# keychange.net
KiCad netlist of a schematic drawn in EAGLE
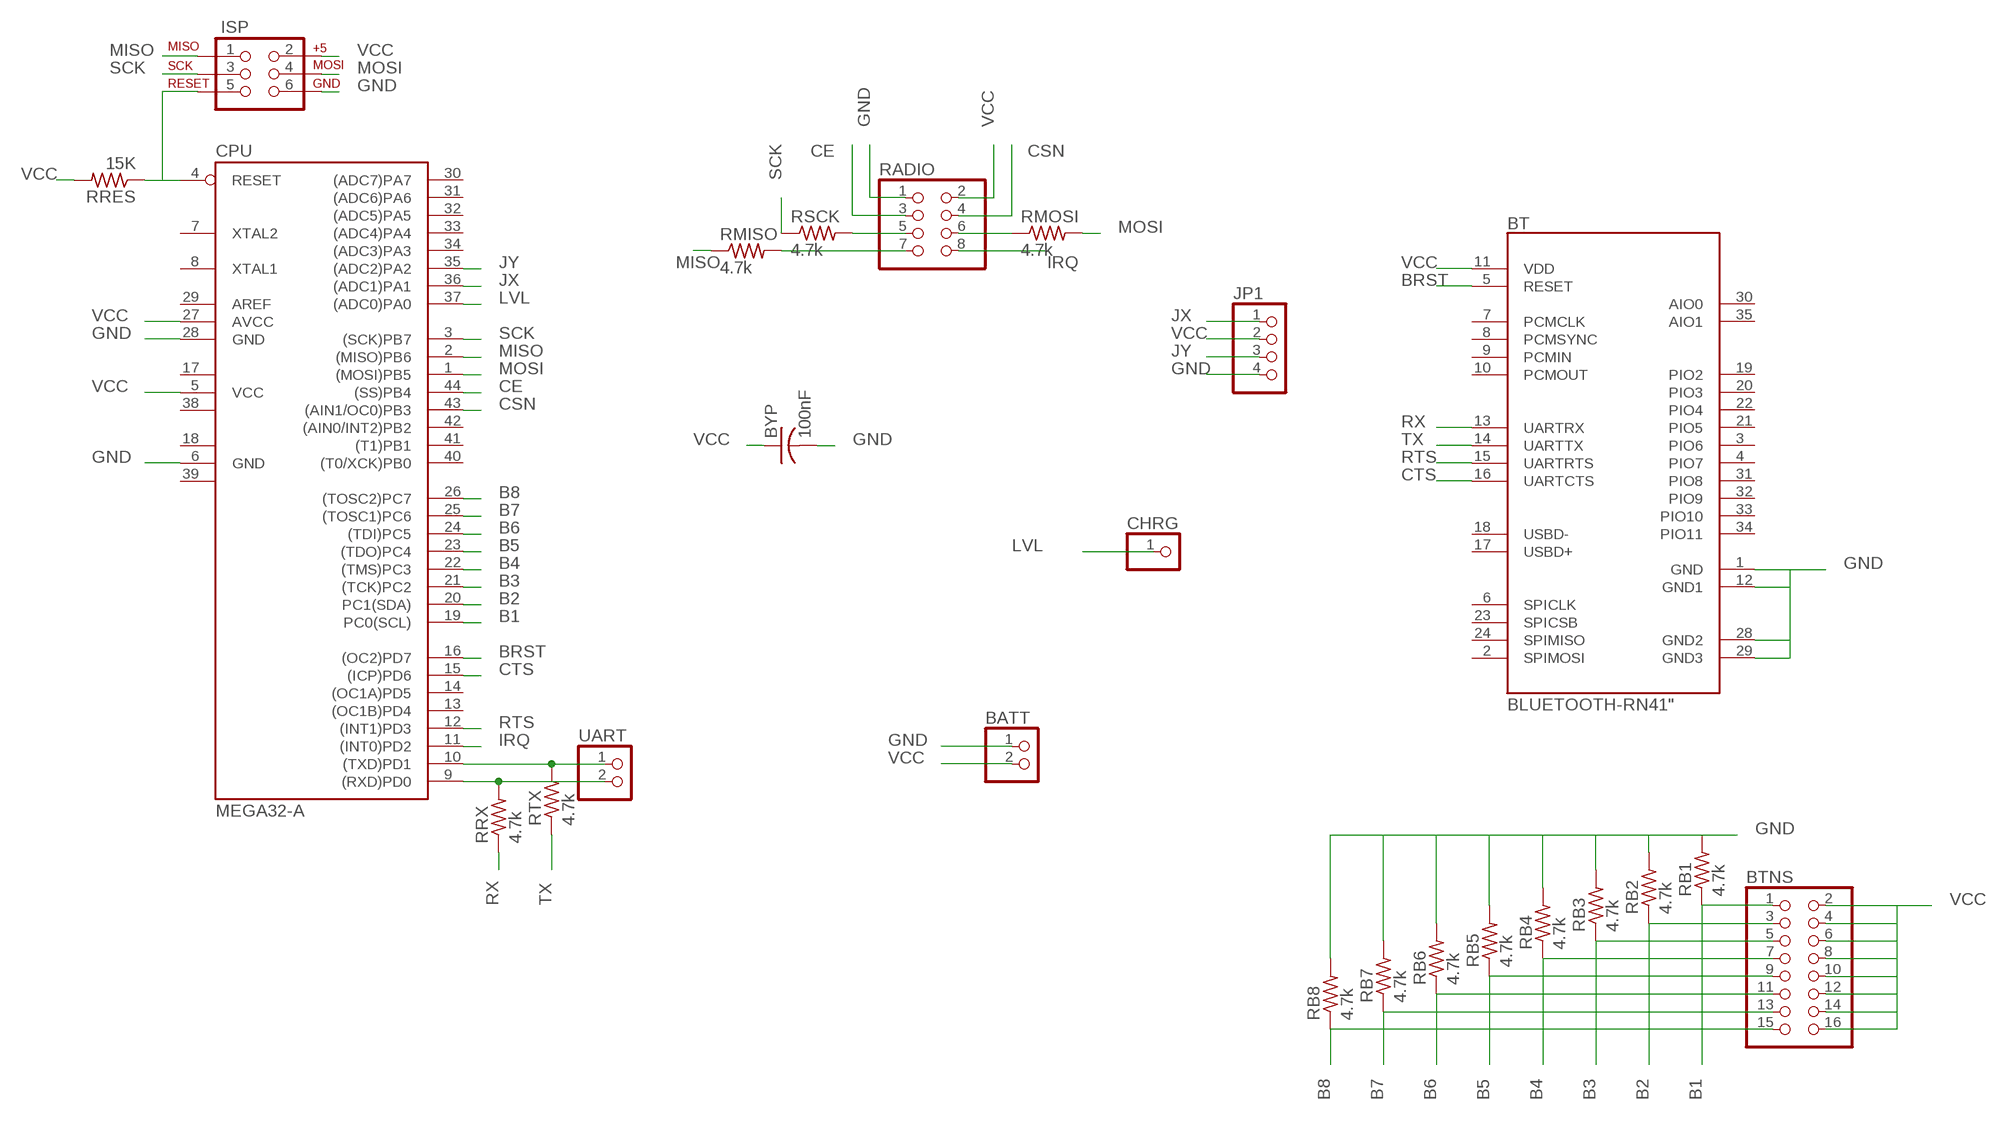
[diagram p0: schematic, sheet 1]

(export (version "E")
  (design (tool "Eeschema 10.0.6"))
  (components
    (comp (ref "BATT")
      (value "PINHD-1X2")
      (footprint "eagle-import:1X02")
      (libsource (lib "eagle-import") (part "PINHD-1X2"))
    )
    (comp (ref "BT")
      (value "BLUETOOTH-RN41\"")
      (footprint "eagle-import:RN41")
      (libsource (lib "eagle-import") (part "BLUETOOTH-RN41{dblquote}"))
    )
    (comp (ref "BTNS")
      (value "PINHD-2X8")
      (footprint "eagle-import:2X08")
      (libsource (lib "eagle-import") (part "PINHD-2X8"))
    )
    (comp (ref "BYP")
      (value "100nF")
      (footprint "eagle-import:C0603")
      (libsource (lib "eagle-import") (part "C-USC0603"))
    )
    (comp (ref "CHRG")
      (value "PINHD-1X1")
      (footprint "eagle-import:1X01")
      (libsource (lib "eagle-import") (part "PINHD-1X1"))
    )
    (comp (ref "CPU")
      (value "MEGA32-A")
      (footprint "eagle-import:TQFP44")
      (fields (field (name "MPN") "ATMEGA32-16AU"))
      (libsource (lib "eagle-import") (part "MEGA32-A"))
    )
    (comp (ref "ISP")
      (value "AVR_SPI_PRG_62X3_LOCK")
      (footprint "eagle-import:2X3_LOCK")
      (libsource (lib "eagle-import") (part "AVR_SPI_PRG_62X3_LOCK"))
    )
    (comp (ref "JP1")
      (value "PINHD-1X4")
      (footprint "eagle-import:1X04")
      (libsource (lib "eagle-import") (part "PINHD-1X4"))
    )
    (comp (ref "RADIO")
      (value "PINHD-2X4")
      (footprint "eagle-import:2X04")
      (libsource (lib "eagle-import") (part "PINHD-2X4"))
    )
    (comp (ref "RB1")
      (value "4.7k")
      (footprint "eagle-import:R0603")
      (libsource (lib "eagle-import") (part "R-US_R0603"))
    )
    (comp (ref "RB2")
      (value "4.7k")
      (footprint "eagle-import:R0603")
      (libsource (lib "eagle-import") (part "R-US_R0603"))
    )
    (comp (ref "RB3")
      (value "4.7k")
      (footprint "eagle-import:R0603")
      (libsource (lib "eagle-import") (part "R-US_R0603"))
    )
    (comp (ref "RB4")
      (value "4.7k")
      (footprint "eagle-import:R0603")
      (libsource (lib "eagle-import") (part "R-US_R0603"))
    )
    (comp (ref "RB5")
      (value "4.7k")
      (footprint "eagle-import:R0603")
      (libsource (lib "eagle-import") (part "R-US_R0603"))
    )
    (comp (ref "RB6")
      (value "4.7k")
      (footprint "eagle-import:R0603")
      (libsource (lib "eagle-import") (part "R-US_R0603"))
    )
    (comp (ref "RB7")
      (value "4.7k")
      (footprint "eagle-import:R0603")
      (libsource (lib "eagle-import") (part "R-US_R0603"))
    )
    (comp (ref "RB8")
      (value "4.7k")
      (footprint "eagle-import:R0603")
      (libsource (lib "eagle-import") (part "R-US_R0603"))
    )
    (comp (ref "RMISO")
      (value "4.7k")
      (footprint "eagle-import:R0603")
      (libsource (lib "eagle-import") (part "R-US_R0603"))
    )
    (comp (ref "RMOSI")
      (value "4.7k")
      (footprint "eagle-import:R0603")
      (libsource (lib "eagle-import") (part "R-US_R0603"))
    )
    (comp (ref "RRES")
      (value "15K")
      (footprint "eagle-import:R0603")
      (libsource (lib "eagle-import") (part "R-US_R0603"))
    )
    (comp (ref "RRX")
      (value "4.7k")
      (footprint "eagle-import:R0603")
      (libsource (lib "eagle-import") (part "R-US_R0603"))
    )
    (comp (ref "RSCK")
      (value "4.7k")
      (footprint "eagle-import:R0603")
      (libsource (lib "eagle-import") (part "R-US_R0603"))
    )
    (comp (ref "RTX")
      (value "4.7k")
      (footprint "eagle-import:R0603")
      (libsource (lib "eagle-import") (part "R-US_R0603"))
    )
    (comp (ref "UART")
      (value "PINHD-1X2")
      (footprint "eagle-import:1X02")
      (libsource (lib "eagle-import") (part "PINHD-1X2"))
    )
  )
  (nets
    (net (code "1") (name "/B1") (class "Default")
      (node (ref "BTNS") (pin "1") (pinfunction "1_1") (pintype "passive"))
      (node (ref "CPU") (pin "19") (pinfunction "PC0(SCL)_19") (pintype "bidirectional"))
      (node (ref "RB1") (pin "1") (pinfunction "1_1") (pintype "passive"))
    )
    (net (code "2") (name "/B2") (class "Default")
      (node (ref "BTNS") (pin "3") (pinfunction "3_3") (pintype "passive"))
      (node (ref "CPU") (pin "20") (pinfunction "PC1(SDA)_20") (pintype "bidirectional"))
      (node (ref "RB2") (pin "1") (pinfunction "1_1") (pintype "passive"))
    )
    (net (code "3") (name "/B3") (class "Default")
      (node (ref "BTNS") (pin "5") (pinfunction "5_5") (pintype "passive"))
      (node (ref "CPU") (pin "21") (pinfunction "(TCK)PC2_21") (pintype "bidirectional"))
      (node (ref "RB3") (pin "1") (pinfunction "1_1") (pintype "passive"))
    )
    (net (code "4") (name "/B4") (class "Default")
      (node (ref "BTNS") (pin "7") (pinfunction "7_7") (pintype "passive"))
      (node (ref "CPU") (pin "22") (pinfunction "(TMS)PC3_22") (pintype "bidirectional"))
      (node (ref "RB4") (pin "1") (pinfunction "1_1") (pintype "passive"))
    )
    (net (code "5") (name "/B5") (class "Default")
      (node (ref "BTNS") (pin "9") (pinfunction "9_9") (pintype "passive"))
      (node (ref "CPU") (pin "23") (pinfunction "(TDO)PC4_23") (pintype "bidirectional"))
      (node (ref "RB5") (pin "1") (pinfunction "1_1") (pintype "passive"))
    )
    (net (code "6") (name "/B6") (class "Default")
      (node (ref "BTNS") (pin "11") (pinfunction "11_11") (pintype "passive"))
      (node (ref "CPU") (pin "24") (pinfunction "(TDI)PC5_24") (pintype "bidirectional"))
      (node (ref "RB6") (pin "1") (pinfunction "1_1") (pintype "passive"))
    )
    (net (code "7") (name "/B7") (class "Default")
      (node (ref "BTNS") (pin "13") (pinfunction "13_13") (pintype "passive"))
      (node (ref "CPU") (pin "25") (pinfunction "(TOSC1)PC6_25") (pintype "bidirectional"))
      (node (ref "RB7") (pin "1") (pinfunction "1_1") (pintype "passive"))
    )
    (net (code "8") (name "/B8") (class "Default")
      (node (ref "BTNS") (pin "15") (pinfunction "15_15") (pintype "passive"))
      (node (ref "CPU") (pin "26") (pinfunction "(TOSC2)PC7_26") (pintype "bidirectional"))
      (node (ref "RB8") (pin "1") (pinfunction "1_1") (pintype "passive"))
    )
    (net (code "9") (name "/BRST") (class "Default")
      (node (ref "BT") (pin "5") (pinfunction "RESET_5") (pintype "bidirectional"))
      (node (ref "CPU") (pin "16") (pinfunction "(OC2)PD7_16") (pintype "bidirectional"))
    )
    (net (code "10") (name "/CE") (class "Default")
      (node (ref "CPU") (pin "44") (pinfunction "(SS)PB4_44") (pintype "bidirectional"))
      (node (ref "RADIO") (pin "3") (pinfunction "3_3") (pintype "passive"))
    )
    (net (code "11") (name "/CSN") (class "Default")
      (node (ref "CPU") (pin "43") (pinfunction "(AIN1/OC0)PB3_43") (pintype "bidirectional"))
      (node (ref "RADIO") (pin "4") (pinfunction "4_4") (pintype "passive"))
    )
    (net (code "12") (name "/CTS") (class "Default")
      (node (ref "BT") (pin "16") (pinfunction "UARTCTS_16") (pintype "bidirectional"))
      (node (ref "CPU") (pin "15") (pinfunction "(ICP)PD6_15") (pintype "bidirectional"))
    )
    (net (code "13") (name "/GND") (class "Default")
      (node (ref "BATT") (pin "1") (pinfunction "1_1") (pintype "passive"))
      (node (ref "BT") (pin "1") (pinfunction "GND_1") (pintype "bidirectional"))
      (node (ref "BT") (pin "12") (pinfunction "GND1_12") (pintype "bidirectional"))
      (node (ref "BT") (pin "28") (pinfunction "GND2_28") (pintype "bidirectional"))
      (node (ref "BT") (pin "29") (pinfunction "GND3_29") (pintype "bidirectional"))
      (node (ref "BYP") (pin "2") (pinfunction "2_2") (pintype "passive"))
      (node (ref "CPU") (pin "28") (pinfunction "GND_28") (pintype "power_in"))
      (node (ref "CPU") (pin "6") (pinfunction "GND_6") (pintype "power_in"))
      (node (ref "ISP") (pin "6") (pinfunction "6_6") (pintype "passive"))
      (node (ref "JP1") (pin "4") (pinfunction "4_4") (pintype "passive"))
      (node (ref "RADIO") (pin "1") (pinfunction "1_1") (pintype "passive"))
      (node (ref "RB1") (pin "2") (pinfunction "2_2") (pintype "passive"))
      (node (ref "RB2") (pin "2") (pinfunction "2_2") (pintype "passive"))
      (node (ref "RB3") (pin "2") (pinfunction "2_2") (pintype "passive"))
      (node (ref "RB4") (pin "2") (pinfunction "2_2") (pintype "passive"))
      (node (ref "RB5") (pin "2") (pinfunction "2_2") (pintype "passive"))
      (node (ref "RB6") (pin "2") (pinfunction "2_2") (pintype "passive"))
      (node (ref "RB7") (pin "2") (pinfunction "2_2") (pintype "passive"))
      (node (ref "RB8") (pin "2") (pinfunction "2_2") (pintype "passive"))
    )
    (net (code "14") (name "/GND1") (class "Default")
      (node (ref "CPU") (pin "18") (pinfunction "GND1_18") (pintype "power_in"))
    )
    (net (code "15") (name "/GND2") (class "Default")
      (node (ref "CPU") (pin "39") (pinfunction "GND2_39") (pintype "power_in"))
    )
    (net (code "16") (name "/IRQ") (class "Default")
      (node (ref "CPU") (pin "11") (pinfunction "(INT0)PD2_11") (pintype "bidirectional"))
      (node (ref "RADIO") (pin "8") (pinfunction "8_8") (pintype "passive"))
    )
    (net (code "17") (name "/JX") (class "Default")
      (node (ref "CPU") (pin "36") (pinfunction "(ADC1)PA1_36") (pintype "bidirectional"))
      (node (ref "JP1") (pin "1") (pinfunction "1_1") (pintype "passive"))
    )
    (net (code "18") (name "/JY") (class "Default")
      (node (ref "CPU") (pin "35") (pinfunction "(ADC2)PA2_35") (pintype "bidirectional"))
      (node (ref "JP1") (pin "3") (pinfunction "3_3") (pintype "passive"))
    )
    (net (code "19") (name "/LVL") (class "Default")
      (node (ref "CHRG") (pin "1") (pinfunction "1_1") (pintype "passive"))
      (node (ref "CPU") (pin "37") (pinfunction "(ADC0)PA0_37") (pintype "bidirectional"))
    )
    (net (code "20") (name "/MISO") (class "Default")
      (node (ref "CPU") (pin "2") (pinfunction "(MISO)PB6_2") (pintype "bidirectional"))
      (node (ref "ISP") (pin "1") (pinfunction "1_1") (pintype "passive"))
      (node (ref "RMISO") (pin "1") (pinfunction "1_1") (pintype "passive"))
    )
    (net (code "21") (name "/MOSI") (class "Default")
      (node (ref "CPU") (pin "1") (pinfunction "(MOSI)PB5_1") (pintype "bidirectional"))
      (node (ref "ISP") (pin "4") (pinfunction "4_4") (pintype "passive"))
      (node (ref "RMOSI") (pin "2") (pinfunction "2_2") (pintype "passive"))
    )
    (net (code "22") (name "/RTS") (class "Default")
      (node (ref "BT") (pin "15") (pinfunction "UARTRTS_15") (pintype "bidirectional"))
      (node (ref "CPU") (pin "12") (pinfunction "(INT1)PD3_12") (pintype "bidirectional"))
    )
    (net (code "23") (name "/RX") (class "Default")
      (node (ref "BT") (pin "13") (pinfunction "UARTRX_13") (pintype "bidirectional"))
      (node (ref "RRX") (pin "1") (pinfunction "1_1") (pintype "passive"))
    )
    (net (code "24") (name "/SCK") (class "Default")
      (node (ref "CPU") (pin "3") (pinfunction "(SCK)PB7_3") (pintype "bidirectional"))
      (node (ref "ISP") (pin "3") (pinfunction "3_3") (pintype "passive"))
      (node (ref "RSCK") (pin "1") (pinfunction "1_1") (pintype "passive"))
    )
    (net (code "25") (name "/TX") (class "Default")
      (node (ref "BT") (pin "14") (pinfunction "UARTTX_14") (pintype "bidirectional"))
      (node (ref "RTX") (pin "1") (pinfunction "1_1") (pintype "passive"))
    )
    (net (code "26") (name "/VCC") (class "Default")
      (node (ref "BATT") (pin "2") (pinfunction "2_2") (pintype "passive"))
      (node (ref "BT") (pin "11") (pinfunction "VDD_11") (pintype "bidirectional"))
      (node (ref "BTNS") (pin "10") (pinfunction "10_10") (pintype "passive"))
      (node (ref "BTNS") (pin "12") (pinfunction "12_12") (pintype "passive"))
      (node (ref "BTNS") (pin "14") (pinfunction "14_14") (pintype "passive"))
      (node (ref "BTNS") (pin "16") (pinfunction "16_16") (pintype "passive"))
      (node (ref "BTNS") (pin "2") (pinfunction "2_2") (pintype "passive"))
      (node (ref "BTNS") (pin "4") (pinfunction "4_4") (pintype "passive"))
      (node (ref "BTNS") (pin "6") (pinfunction "6_6") (pintype "passive"))
      (node (ref "BTNS") (pin "8") (pinfunction "8_8") (pintype "passive"))
      (node (ref "BYP") (pin "1") (pinfunction "1_1") (pintype "passive"))
      (node (ref "CPU") (pin "27") (pinfunction "AVCC_27") (pintype "power_in"))
      (node (ref "CPU") (pin "5") (pinfunction "VCC_5") (pintype "power_in"))
      (node (ref "ISP") (pin "2") (pinfunction "2_2") (pintype "passive"))
      (node (ref "JP1") (pin "2") (pinfunction "2_2") (pintype "passive"))
      (node (ref "RADIO") (pin "2") (pinfunction "2_2") (pintype "passive"))
      (node (ref "RRES") (pin "2") (pinfunction "2_2") (pintype "passive"))
    )
    (net (code "27") (name "/VCC1") (class "Default")
      (node (ref "CPU") (pin "17") (pinfunction "VCC1_17") (pintype "power_in"))
    )
    (net (code "28") (name "/VCC2") (class "Default")
      (node (ref "CPU") (pin "38") (pinfunction "VCC2_38") (pintype "power_in"))
    )
    (net (code "29") (name "Net-(CPU-(RXD)PD0)") (class "Default")
      (node (ref "CPU") (pin "9") (pinfunction "(RXD)PD0_9") (pintype "bidirectional"))
      (node (ref "RRX") (pin "2") (pinfunction "2_2") (pintype "passive"))
      (node (ref "UART") (pin "2") (pinfunction "2_2") (pintype "passive"))
    )
    (net (code "30") (name "Net-(CPU-(TXD)PD1)") (class "Default")
      (node (ref "CPU") (pin "10") (pinfunction "(TXD)PD1_10") (pintype "bidirectional"))
      (node (ref "RTX") (pin "2") (pinfunction "2_2") (pintype "passive"))
      (node (ref "UART") (pin "1") (pinfunction "1_1") (pintype "passive"))
    )
    (net (code "31") (name "Net-(CPU-RESET)") (class "Default")
      (node (ref "CPU") (pin "4") (pinfunction "RESET_4") (pintype "input"))
      (node (ref "ISP") (pin "5") (pinfunction "5_5") (pintype "passive"))
      (node (ref "RRES") (pin "1") (pinfunction "1_1") (pintype "passive"))
    )
    (net (code "32") (name "Net-(RADIO-Pad5)") (class "Default")
      (node (ref "RADIO") (pin "5") (pinfunction "5_5") (pintype "passive"))
      (node (ref "RSCK") (pin "2") (pinfunction "2_2") (pintype "passive"))
    )
    (net (code "33") (name "Net-(RADIO-Pad6)") (class "Default")
      (node (ref "RADIO") (pin "6") (pinfunction "6_6") (pintype "passive"))
      (node (ref "RMOSI") (pin "1") (pinfunction "1_1") (pintype "passive"))
    )
    (net (code "34") (name "Net-(RADIO-Pad7)") (class "Default")
      (node (ref "RADIO") (pin "7") (pinfunction "7_7") (pintype "passive"))
      (node (ref "RMISO") (pin "2") (pinfunction "2_2") (pintype "passive"))
    )
    (net (code "35") (name "unconnected-(BT-AIO0-Pad30)") (class "Default")
      (node (ref "BT") (pin "30") (pinfunction "AIO0_30") (pintype "bidirectional"))
    )
    (net (code "36") (name "unconnected-(BT-AIO1-Pad35)") (class "Default")
      (node (ref "BT") (pin "35") (pinfunction "AIO1_35") (pintype "bidirectional"))
    )
    (net (code "37") (name "unconnected-(BT-PCMCLK-Pad7)") (class "Default")
      (node (ref "BT") (pin "7") (pinfunction "PCMCLK_7") (pintype "bidirectional"))
    )
    (net (code "38") (name "unconnected-(BT-PCMIN-Pad9)") (class "Default")
      (node (ref "BT") (pin "9") (pinfunction "PCMIN_9") (pintype "bidirectional"))
    )
    (net (code "39") (name "unconnected-(BT-PCMOUT-Pad10)") (class "Default")
      (node (ref "BT") (pin "10") (pinfunction "PCMOUT_10") (pintype "bidirectional"))
    )
    (net (code "40") (name "unconnected-(BT-PCMSYNC-Pad8)") (class "Default")
      (node (ref "BT") (pin "8") (pinfunction "PCMSYNC_8") (pintype "bidirectional"))
    )
    (net (code "41") (name "unconnected-(BT-PIO2-Pad19)") (class "Default")
      (node (ref "BT") (pin "19") (pinfunction "PIO2_19") (pintype "bidirectional"))
    )
    (net (code "42") (name "unconnected-(BT-PIO3-Pad20)") (class "Default")
      (node (ref "BT") (pin "20") (pinfunction "PIO3_20") (pintype "bidirectional"))
    )
    (net (code "43") (name "unconnected-(BT-PIO4-Pad22)") (class "Default")
      (node (ref "BT") (pin "22") (pinfunction "PIO4_22") (pintype "bidirectional"))
    )
    (net (code "44") (name "unconnected-(BT-PIO5-Pad21)") (class "Default")
      (node (ref "BT") (pin "21") (pinfunction "PIO5_21") (pintype "bidirectional"))
    )
    (net (code "45") (name "unconnected-(BT-PIO6-Pad3)") (class "Default")
      (node (ref "BT") (pin "3") (pinfunction "PIO6_3") (pintype "bidirectional"))
    )
    (net (code "46") (name "unconnected-(BT-PIO7-Pad4)") (class "Default")
      (node (ref "BT") (pin "4") (pinfunction "PIO7_4") (pintype "bidirectional"))
    )
    (net (code "47") (name "unconnected-(BT-PIO8-Pad31)") (class "Default")
      (node (ref "BT") (pin "31") (pinfunction "PIO8_31") (pintype "bidirectional"))
    )
    (net (code "48") (name "unconnected-(BT-PIO9-Pad32)") (class "Default")
      (node (ref "BT") (pin "32") (pinfunction "PIO9_32") (pintype "bidirectional"))
    )
    (net (code "49") (name "unconnected-(BT-PIO10-Pad33)") (class "Default")
      (node (ref "BT") (pin "33") (pinfunction "PIO10_33") (pintype "bidirectional"))
    )
    (net (code "50") (name "unconnected-(BT-PIO11-Pad34)") (class "Default")
      (node (ref "BT") (pin "34") (pinfunction "PIO11_34") (pintype "bidirectional"))
    )
    (net (code "51") (name "unconnected-(BT-SPICLK-Pad6)") (class "Default")
      (node (ref "BT") (pin "6") (pinfunction "SPICLK_6") (pintype "bidirectional"))
    )
    (net (code "52") (name "unconnected-(BT-SPICSB-Pad23)") (class "Default")
      (node (ref "BT") (pin "23") (pinfunction "SPICSB_23") (pintype "bidirectional"))
    )
    (net (code "53") (name "unconnected-(BT-SPIMISO-Pad24)") (class "Default")
      (node (ref "BT") (pin "24") (pinfunction "SPIMISO_24") (pintype "bidirectional"))
    )
    (net (code "54") (name "unconnected-(BT-SPIMOSI-Pad2)") (class "Default")
      (node (ref "BT") (pin "2") (pinfunction "SPIMOSI_2") (pintype "bidirectional"))
    )
    (net (code "55") (name "unconnected-(BT-USBD+-Pad17)") (class "Default")
      (node (ref "BT") (pin "17") (pinfunction "USBD+_17") (pintype "bidirectional"))
    )
    (net (code "56") (name "unconnected-(BT-USBD--Pad18)") (class "Default")
      (node (ref "BT") (pin "18") (pinfunction "USBD-_18") (pintype "bidirectional"))
    )
    (net (code "57") (name "unconnected-(CPU-(ADC3)PA3-Pad34)") (class "Default")
      (node (ref "CPU") (pin "34") (pinfunction "(ADC3)PA3_34") (pintype "bidirectional"))
    )
    (net (code "58") (name "unconnected-(CPU-(ADC4)PA4-Pad33)") (class "Default")
      (node (ref "CPU") (pin "33") (pinfunction "(ADC4)PA4_33") (pintype "bidirectional"))
    )
    (net (code "59") (name "unconnected-(CPU-(ADC5)PA5-Pad32)") (class "Default")
      (node (ref "CPU") (pin "32") (pinfunction "(ADC5)PA5_32") (pintype "bidirectional"))
    )
    (net (code "60") (name "unconnected-(CPU-(ADC6)PA6-Pad31)") (class "Default")
      (node (ref "CPU") (pin "31") (pinfunction "(ADC6)PA6_31") (pintype "bidirectional"))
    )
    (net (code "61") (name "unconnected-(CPU-(ADC7)PA7-Pad30)") (class "Default")
      (node (ref "CPU") (pin "30") (pinfunction "(ADC7)PA7_30") (pintype "bidirectional"))
    )
    (net (code "62") (name "unconnected-(CPU-(AIN0{slash}INT2)PB2-Pad42)") (class "Default")
      (node (ref "CPU") (pin "42") (pinfunction "(AIN0/INT2)PB2_42") (pintype "bidirectional"))
    )
    (net (code "63") (name "unconnected-(CPU-(OC1A)PD5-Pad14)") (class "Default")
      (node (ref "CPU") (pin "14") (pinfunction "(OC1A)PD5_14") (pintype "bidirectional"))
    )
    (net (code "64") (name "unconnected-(CPU-(OC1B)PD4-Pad13)") (class "Default")
      (node (ref "CPU") (pin "13") (pinfunction "(OC1B)PD4_13") (pintype "bidirectional"))
    )
    (net (code "65") (name "unconnected-(CPU-(T0{slash}XCK)PB0-Pad40)") (class "Default")
      (node (ref "CPU") (pin "40") (pinfunction "(T0/XCK)PB0_40") (pintype "bidirectional"))
    )
    (net (code "66") (name "unconnected-(CPU-(T1)PB1-Pad41)") (class "Default")
      (node (ref "CPU") (pin "41") (pinfunction "(T1)PB1_41") (pintype "bidirectional"))
    )
    (net (code "67") (name "unconnected-(CPU-AREF-Pad29)") (class "Default")
      (node (ref "CPU") (pin "29") (pinfunction "AREF_29") (pintype "passive"))
    )
    (net (code "68") (name "unconnected-(CPU-XTAL1-Pad8)") (class "Default")
      (node (ref "CPU") (pin "8") (pinfunction "XTAL1_8") (pintype "bidirectional"))
    )
    (net (code "69") (name "unconnected-(CPU-XTAL2-Pad7)") (class "Default")
      (node (ref "CPU") (pin "7") (pinfunction "XTAL2_7") (pintype "bidirectional"))
    )
  )
)
